# MirZ21.net
KiCad netlist of a schematic drawn in EAGLE
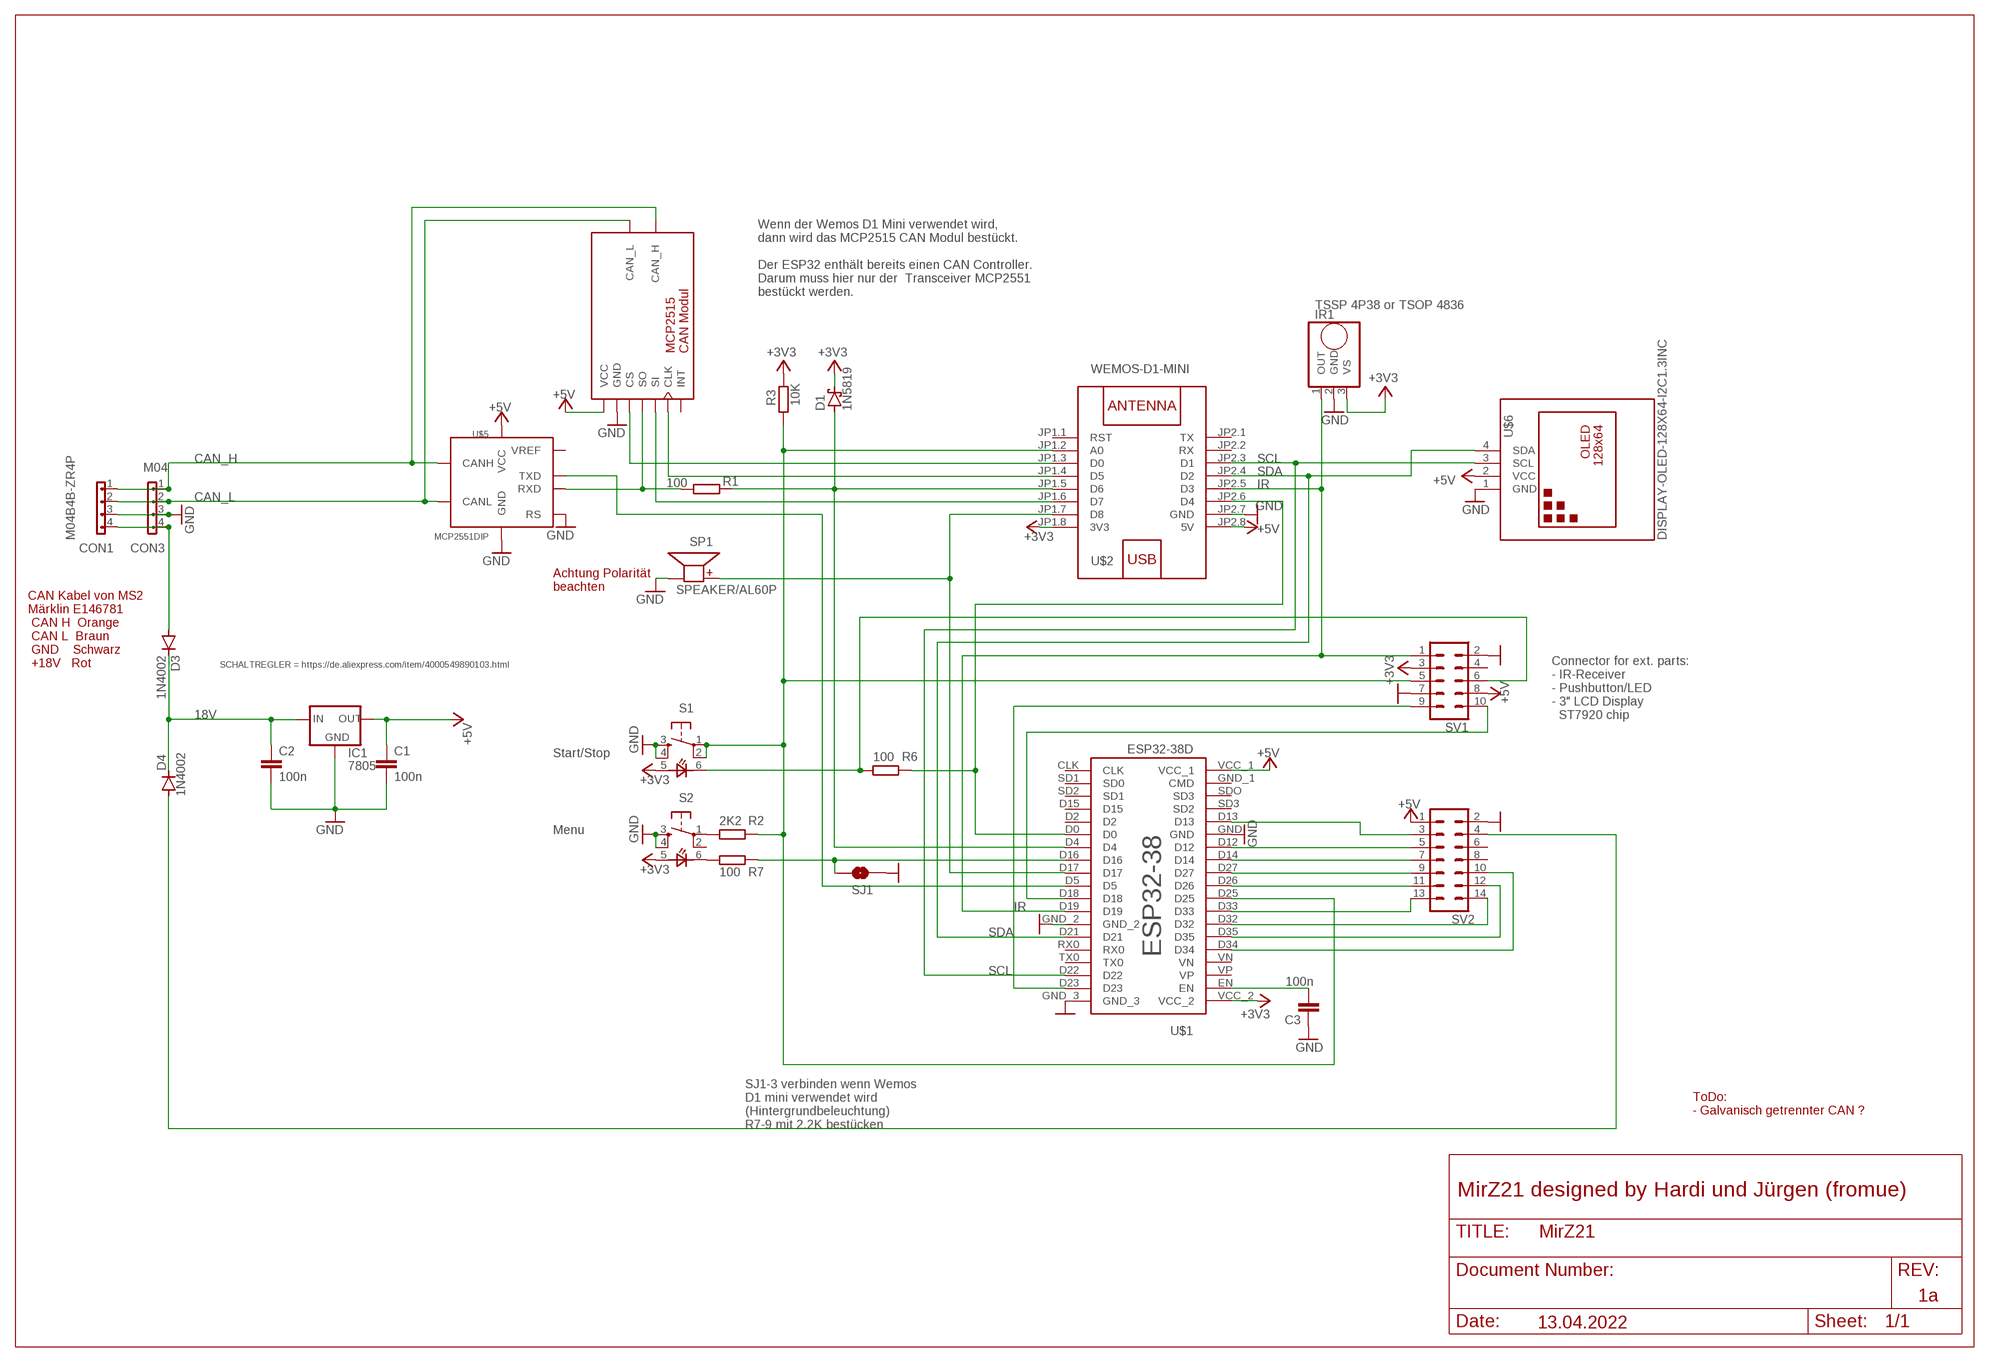
[diagram p0: schematic, sheet 1]

(export (version "E")
  (design (tool "Eeschema 10.0.6"))
  (components
    (comp (ref "C1")
      (value "100n")
      (footprint "eagle-import:C025-025X050")
      (libsource (lib "eagle-import") (part "C-EU025-025X050"))
    )
    (comp (ref "C2")
      (value "100n")
      (footprint "eagle-import:C025-025X050")
      (libsource (lib "eagle-import") (part "C-EU025-025X050"))
    )
    (comp (ref "C3")
      (value "100n")
      (footprint "eagle-import:C025-025X050")
      (libsource (lib "eagle-import") (part "C-EU025-025X050"))
    )
    (comp (ref "CAN1")
      (value "MCP2515_CAN_CUTCUT")
      (footprint "eagle-import:MCP2515_CAN_CUT")
      (libsource (lib "eagle-import") (part "MCP2515_CAN_CUTCUT"))
    )
    (comp (ref "CON1")
      (value "M04B4B-ZR4P")
      (footprint "eagle-import:B4B-ZR4P")
      (libsource (lib "eagle-import") (part "M04B4B-ZR4P"))
    )
    (comp (ref "CON3")
      (value "M04")
      (footprint "eagle-import:1X04")
      (libsource (lib "eagle-import") (part "M04"))
    )
    (comp (ref "D1")
      (value "1N5819")
      (footprint "eagle-import:DO41-7.6")
      (libsource (lib "eagle-import") (part "1N581"))
    )
    (comp (ref "D3")
      (value "1N4002")
      (footprint "eagle-import:DO41-10")
      (libsource (lib "eagle-import") (part "1N4004"))
    )
    (comp (ref "D4")
      (value "1N4002")
      (footprint "eagle-import:DO41-10")
      (libsource (lib "eagle-import") (part "1N4004"))
    )
    (comp (ref "IC1")
      (value "7805")
      (footprint "eagle-import:HX1314G")
      (fields (field (name "SCHALTREGLER") "https://de.aliexpress.com/item/4000549890103.html"))
      (libsource (lib "eagle-import") (part "78XXSSTEPDOWN"))
    )
    (comp (ref "IR1")
      (value "TSSP 4P38 or TSOP 4836")
      (footprint "eagle-import:TSSP4P38")
      (libsource (lib "eagle-import") (part "TSSP4P38"))
    )
    (comp (ref "R1")
      (value "100")
      (footprint "eagle-import:0204_7")
      (libsource (lib "eagle-import") (part "R0204/7"))
    )
    (comp (ref "R2")
      (value "2K2")
      (footprint "eagle-import:0204_7")
      (libsource (lib "eagle-import") (part "R0204/7"))
    )
    (comp (ref "R3")
      (value "10K")
      (footprint "eagle-import:0204_7")
      (libsource (lib "eagle-import") (part "R0204/7"))
    )
    (comp (ref "R6")
      (value "100")
      (footprint "eagle-import:0204_7")
      (libsource (lib "eagle-import") (part "R0204/7"))
    )
    (comp (ref "R7")
      (value "100")
      (footprint "eagle-import:0204_7")
      (libsource (lib "eagle-import") (part "R0204/7"))
    )
    (comp (ref "S1")
      (value "TASTER_LEDTC-1198-B")
      (footprint "eagle-import:TASTER_LED")
      (libsource (lib "eagle-import") (part "TASTER_LEDTC-1198-B"))
    )
    (comp (ref "S2")
      (value "TASTER_LEDTC-1198-B")
      (footprint "eagle-import:TASTER_LED")
      (libsource (lib "eagle-import") (part "TASTER_LEDTC-1198-B"))
    )
    (comp (ref "SJ1")
      (value "SOLDERJUMPERNO")
      (footprint "eagle-import:SJ_2S-NO")
      (libsource (lib "eagle-import") (part "SOLDERJUMPERNO"))
    )
    (comp (ref "SP1")
      (value "SPEAKER/AL60P")
      (footprint "eagle-import:RMP-14SP")
      (libsource (lib "eagle-import") (part "SPEAKER/AL60P"))
    )
    (comp (ref "SV1")
      (value "ML10")
      (footprint "eagle-import:ML10")
      (libsource (lib "eagle-import") (part "ML10"))
    )
    (comp (ref "SV2")
      (value "ML14")
      (footprint "eagle-import:ML14")
      (libsource (lib "eagle-import") (part "ML14"))
    )
    (comp (ref "U$1")
      (value "ESP32-38D")
      (footprint "eagle-import:ESP32-38D")
      (libsource (lib "eagle-import") (part "ESP32-38D"))
    )
    (comp (ref "U$2")
      (value "WEMOS-D1-MINI")
      (footprint "eagle-import:WEMOS-D1-MINI")
      (libsource (lib "eagle-import") (part "WEMOS-D1-MINI"))
    )
    (comp (ref "U$5")
      (value "MCP2551DIP")
      (footprint "eagle-import:DIP08")
      (libsource (lib "eagle-import") (part "MCP2551DIP"))
    )
    (comp (ref "U$6")
      (value "DISPLAY-OLED-128X64-I2C1.3INC")
      (footprint "eagle-import:DISPLAY-OLED-128X64-I2C-1.3")
      (libsource (lib "eagle-import") (part "DISPLAY-OLED-128X64-I2C1.3INC"))
    )
  )
  (nets
    (net (code "1") (name "+3V3") (class "Default")
      (node (ref "D1") (pin "C") (pinfunction "C_C") (pintype "passive"))
      (node (ref "IR1") (pin "3") (pinfunction "VS_3") (pintype "power_in"))
      (node (ref "R3") (pin "2") (pinfunction "2_2") (pintype "passive"))
      (node (ref "S1") (pin "5") (pinfunction "+_5") (pintype "input"))
      (node (ref "S2") (pin "5") (pinfunction "+_5") (pintype "input"))
      (node (ref "SV1") (pin "3") (pinfunction "3_3") (pintype "passive"))
      (node (ref "U$1") (pin "VCC_2") (pinfunction "VCC_2_VCC_2") (pintype "power_in"))
      (node (ref "U$2") (pin "JP1.8") (pinfunction "3V3_JP1.8") (pintype "power_in"))
    )
    (net (code "2") (name "+5V") (class "Default")
      (node (ref "C1") (pin "1") (pinfunction "1_1") (pintype "passive"))
      (node (ref "CAN1") (pin "1") (pinfunction "VCC_1") (pintype "power_in"))
      (node (ref "IC1") (pin "OUT") (pinfunction "OUT_OUT") (pintype "passive"))
      (node (ref "SV1") (pin "8") (pinfunction "8_8") (pintype "passive"))
      (node (ref "SV2") (pin "1") (pinfunction "1_1") (pintype "passive"))
      (node (ref "U$1") (pin "VCC_1") (pinfunction "VCC_1_VCC_1") (pintype "power_in"))
      (node (ref "U$2") (pin "JP2.8") (pinfunction "5V_JP2.8") (pintype "power_in"))
      (node (ref "U$5") (pin "3") (pinfunction "VCC_3") (pintype "power_in"))
      (node (ref "U$6") (pin "2") (pinfunction "VCC_2") (pintype "power_in"))
    )
    (net (code "3") (name "/18V") (class "Default")
      (node (ref "C2") (pin "1") (pinfunction "1_1") (pintype "passive"))
      (node (ref "D3") (pin "C") (pinfunction "C_C") (pintype "passive"))
      (node (ref "D4") (pin "C") (pinfunction "C_C") (pintype "passive"))
      (node (ref "IC1") (pin "IN") (pinfunction "IN_IN") (pintype "input"))
    )
    (net (code "4") (name "/CAN_H") (class "Default")
      (node (ref "CAN1") (pin "9") (pinfunction "CAN_H_9") (pintype "bidirectional"))
      (node (ref "CON1") (pin "1") (pinfunction "1_1") (pintype "passive"))
      (node (ref "CON3") (pin "1") (pinfunction "1_1") (pintype "passive"))
      (node (ref "U$5") (pin "7") (pinfunction "CANH_7") (pintype "bidirectional"))
    )
    (net (code "5") (name "/CAN_L") (class "Default")
      (node (ref "CAN1") (pin "8") (pinfunction "CAN_L_8") (pintype "bidirectional"))
      (node (ref "CON1") (pin "2") (pinfunction "2_2") (pintype "passive"))
      (node (ref "CON3") (pin "2") (pinfunction "2_2") (pintype "passive"))
      (node (ref "U$5") (pin "6") (pinfunction "CANL_6") (pintype "bidirectional"))
    )
    (net (code "6") (name "/IR") (class "Default")
      (node (ref "IR1") (pin "1") (pinfunction "OUT_1") (pintype "output"))
      (node (ref "SV1") (pin "1") (pinfunction "1_1") (pintype "passive"))
      (node (ref "U$1") (pin "D19") (pinfunction "D19_D19") (pintype "bidirectional"))
      (node (ref "U$2") (pin "JP2.5") (pinfunction "D3_JP2.5") (pintype "bidirectional"))
    )
    (net (code "7") (name "/SCL") (class "Default")
      (node (ref "U$1") (pin "D22") (pinfunction "D22_D22") (pintype "bidirectional"))
      (node (ref "U$2") (pin "JP2.3") (pinfunction "D1_JP2.3") (pintype "bidirectional"))
      (node (ref "U$6") (pin "3") (pinfunction "SCL_3") (pintype "bidirectional"))
    )
    (net (code "8") (name "/SDA") (class "Default")
      (node (ref "U$1") (pin "D21") (pinfunction "D21_D21") (pintype "bidirectional"))
      (node (ref "U$2") (pin "JP2.4") (pinfunction "D2_JP2.4") (pintype "bidirectional"))
      (node (ref "U$6") (pin "4") (pinfunction "SDA_4") (pintype "bidirectional"))
    )
    (net (code "9") (name "/VREF") (class "Default")
      (node (ref "U$5") (pin "5") (pinfunction "VREF_5") (pintype "power_in"))
    )
    (net (code "10") (name "GND") (class "Default")
      (node (ref "C1") (pin "2") (pinfunction "2_2") (pintype "passive"))
      (node (ref "C2") (pin "2") (pinfunction "2_2") (pintype "passive"))
      (node (ref "C3") (pin "1") (pinfunction "1_1") (pintype "passive"))
      (node (ref "CAN1") (pin "2") (pinfunction "GND_2") (pintype "power_in"))
      (node (ref "CON1") (pin "3") (pinfunction "3_3") (pintype "passive"))
      (node (ref "CON3") (pin "3") (pinfunction "3_3") (pintype "passive"))
      (node (ref "IC1") (pin "GND") (pinfunction "GND_GND") (pintype "input"))
      (node (ref "IR1") (pin "2") (pinfunction "GND_2") (pintype "power_in"))
      (node (ref "S1") (pin "3") (pinfunction "S_3") (pintype "passive"))
      (node (ref "S1") (pin "4") (pinfunction "S1_4") (pintype "passive"))
      (node (ref "S2") (pin "3") (pinfunction "S_3") (pintype "passive"))
      (node (ref "S2") (pin "4") (pinfunction "S1_4") (pintype "passive"))
      (node (ref "SJ1") (pin "1") (pinfunction "1_1") (pintype "passive"))
      (node (ref "SP1") (pin "2") (pinfunction "-_2") (pintype "passive"))
      (node (ref "SV1") (pin "2") (pinfunction "2_2") (pintype "passive"))
      (node (ref "SV1") (pin "7") (pinfunction "7_7") (pintype "passive"))
      (node (ref "SV2") (pin "2") (pinfunction "2_2") (pintype "passive"))
      (node (ref "U$1") (pin "GND") (pinfunction "GND_GND") (pintype "power_in"))
      (node (ref "U$1") (pin "GND_2") (pinfunction "GND_2_GND_2") (pintype "power_in"))
      (node (ref "U$1") (pin "GND_3") (pinfunction "GND_3_GND_3") (pintype "power_in"))
      (node (ref "U$2") (pin "JP2.7") (pinfunction "GND_JP2.7") (pintype "power_in"))
      (node (ref "U$5") (pin "2") (pinfunction "GND_2") (pintype "power_in"))
      (node (ref "U$5") (pin "8") (pinfunction "RS_8") (pintype "power_in"))
      (node (ref "U$6") (pin "1") (pinfunction "GND_1") (pintype "power_in"))
    )
    (net (code "11") (name "Net-(C3-Pad2)") (class "Default")
      (node (ref "C3") (pin "2") (pinfunction "2_2") (pintype "passive"))
      (node (ref "U$1") (pin "EN") (pinfunction "EN_EN") (pintype "input"))
    )
    (net (code "12") (name "Net-(CAN1-CLK)") (class "Default")
      (node (ref "CAN1") (pin "6") (pinfunction "CLK_6") (pintype "input"))
      (node (ref "U$2") (pin "JP1.4") (pinfunction "D5_JP1.4") (pintype "bidirectional"))
    )
    (net (code "13") (name "Net-(CAN1-CS)") (class "Default")
      (node (ref "CAN1") (pin "3") (pinfunction "CS_3") (pintype "input"))
      (node (ref "U$2") (pin "JP1.3") (pinfunction "D0_JP1.3") (pintype "bidirectional"))
    )
    (net (code "14") (name "Net-(CAN1-SI)") (class "Default")
      (node (ref "CAN1") (pin "5") (pinfunction "SI_5") (pintype "input"))
      (node (ref "U$2") (pin "JP1.6") (pinfunction "D7_JP1.6") (pintype "bidirectional"))
    )
    (net (code "15") (name "Net-(CAN1-SO)") (class "Default")
      (node (ref "CAN1") (pin "4") (pinfunction "SO_4") (pintype "output"))
      (node (ref "R1") (pin "2") (pinfunction "2_2") (pintype "passive"))
      (node (ref "U$5") (pin "4") (pinfunction "RXD_4") (pintype "power_in"))
    )
    (net (code "16") (name "Net-(CON1-Pad4)") (class "Default")
      (node (ref "CON1") (pin "4") (pinfunction "4_4") (pintype "passive"))
      (node (ref "CON3") (pin "4") (pinfunction "4_4") (pintype "passive"))
      (node (ref "D3") (pin "A") (pinfunction "A_A") (pintype "passive"))
    )
    (net (code "17") (name "Net-(D4-PadA)") (class "Default")
      (node (ref "D4") (pin "A") (pinfunction "A_A") (pintype "passive"))
      (node (ref "SV2") (pin "4") (pinfunction "4_4") (pintype "passive"))
    )
    (net (code "18") (name "Net-(R7-Pad1)") (class "Default")
      (node (ref "R7") (pin "1") (pinfunction "1_1") (pintype "passive"))
      (node (ref "SJ1") (pin "2") (pinfunction "2_2") (pintype "passive"))
      (node (ref "U$1") (pin "D16") (pinfunction "D16_D16") (pintype "bidirectional"))
    )
    (net (code "19") (name "Net-(S1--)") (class "Default")
      (node (ref "R6") (pin "2") (pinfunction "2_2") (pintype "passive"))
      (node (ref "S1") (pin "6") (pinfunction "-_6") (pintype "input"))
      (node (ref "SV1") (pin "6") (pinfunction "6_6") (pintype "passive"))
    )
    (net (code "20") (name "Net-(S1-P)") (class "Default")
      (node (ref "R2") (pin "1") (pinfunction "1_1") (pintype "passive"))
      (node (ref "R3") (pin "1") (pinfunction "1_1") (pintype "passive"))
      (node (ref "S1") (pin "1") (pinfunction "P_1") (pintype "passive"))
      (node (ref "S1") (pin "2") (pinfunction "P1_2") (pintype "passive"))
      (node (ref "SV1") (pin "5") (pinfunction "5_5") (pintype "passive"))
      (node (ref "U$1") (pin "D25") (pinfunction "D25_D25") (pintype "bidirectional"))
      (node (ref "U$2") (pin "JP1.2") (pinfunction "A0_JP1.2") (pintype "bidirectional"))
    )
    (net (code "21") (name "Net-(S2--)") (class "Default")
      (node (ref "R7") (pin "2") (pinfunction "2_2") (pintype "passive"))
      (node (ref "S2") (pin "6") (pinfunction "-_6") (pintype "input"))
    )
    (net (code "22") (name "Net-(S2-P)") (class "Default")
      (node (ref "R2") (pin "2") (pinfunction "2_2") (pintype "passive"))
      (node (ref "S2") (pin "1") (pinfunction "P_1") (pintype "passive"))
    )
    (net (code "23") (name "Net-(SP1-+)") (class "Default")
      (node (ref "SP1") (pin "1") (pinfunction "+_1") (pintype "passive"))
      (node (ref "U$1") (pin "D17") (pinfunction "D17_D17") (pintype "bidirectional"))
      (node (ref "U$2") (pin "JP1.7") (pinfunction "D8_JP1.7") (pintype "bidirectional"))
    )
    (net (code "24") (name "Net-(SV1-Pad9)") (class "Default")
      (node (ref "SV1") (pin "9") (pinfunction "9_9") (pintype "passive"))
      (node (ref "U$1") (pin "D23") (pinfunction "D23_D23") (pintype "bidirectional"))
    )
    (net (code "25") (name "Net-(SV1-Pad10)") (class "Default")
      (node (ref "SV1") (pin "10") (pinfunction "10_10") (pintype "passive"))
      (node (ref "U$1") (pin "D18") (pinfunction "D18_D18") (pintype "bidirectional"))
    )
    (net (code "26") (name "Net-(SV2-Pad3)") (class "Default")
      (node (ref "SV2") (pin "3") (pinfunction "3_3") (pintype "passive"))
      (node (ref "U$1") (pin "D13") (pinfunction "D13_D13") (pintype "bidirectional"))
    )
    (net (code "27") (name "Net-(SV2-Pad5)") (class "Default")
      (node (ref "SV2") (pin "5") (pinfunction "5_5") (pintype "passive"))
      (node (ref "U$1") (pin "D12") (pinfunction "D12_D12") (pintype "bidirectional"))
    )
    (net (code "28") (name "Net-(SV2-Pad7)") (class "Default")
      (node (ref "SV2") (pin "7") (pinfunction "7_7") (pintype "passive"))
      (node (ref "U$1") (pin "D14") (pinfunction "D14_D14") (pintype "bidirectional"))
    )
    (net (code "29") (name "Net-(SV2-Pad9)") (class "Default")
      (node (ref "SV2") (pin "9") (pinfunction "9_9") (pintype "passive"))
      (node (ref "U$1") (pin "D27") (pinfunction "D27_D27") (pintype "bidirectional"))
    )
    (net (code "30") (name "Net-(SV2-Pad10)") (class "Default")
      (node (ref "SV2") (pin "10") (pinfunction "10_10") (pintype "passive"))
      (node (ref "U$1") (pin "D34") (pinfunction "D34_D34") (pintype "bidirectional"))
    )
    (net (code "31") (name "Net-(SV2-Pad11)") (class "Default")
      (node (ref "SV2") (pin "11") (pinfunction "11_11") (pintype "passive"))
      (node (ref "U$1") (pin "D26") (pinfunction "D26_D26") (pintype "bidirectional"))
    )
    (net (code "32") (name "Net-(SV2-Pad12)") (class "Default")
      (node (ref "SV2") (pin "12") (pinfunction "12_12") (pintype "passive"))
      (node (ref "U$1") (pin "D35") (pinfunction "D35_D35") (pintype "bidirectional"))
    )
    (net (code "33") (name "Net-(SV2-Pad13)") (class "Default")
      (node (ref "SV2") (pin "13") (pinfunction "13_13") (pintype "passive"))
      (node (ref "U$1") (pin "D33") (pinfunction "D33_D33") (pintype "bidirectional"))
    )
    (net (code "34") (name "Net-(SV2-Pad14)") (class "Default")
      (node (ref "SV2") (pin "14") (pinfunction "14_14") (pintype "passive"))
      (node (ref "U$1") (pin "D32") (pinfunction "D32_D32") (pintype "bidirectional"))
    )
    (net (code "35") (name "Net-(U$2-D4)") (class "Default")
      (node (ref "R6") (pin "1") (pinfunction "1_1") (pintype "passive"))
      (node (ref "U$1") (pin "D0") (pinfunction "D0_D0") (pintype "input"))
      (node (ref "U$2") (pin "JP2.6") (pinfunction "D4_JP2.6") (pintype "bidirectional"))
    )
    (net (code "36") (name "Net-(U$2-D6)") (class "Default")
      (node (ref "D1") (pin "A") (pinfunction "A_A") (pintype "passive"))
      (node (ref "R1") (pin "1") (pinfunction "1_1") (pintype "passive"))
      (node (ref "U$1") (pin "D4") (pinfunction "D4_D4") (pintype "bidirectional"))
      (node (ref "U$2") (pin "JP1.5") (pinfunction "D6_JP1.5") (pintype "bidirectional"))
    )
    (net (code "37") (name "Net-(U$5-TXD)") (class "Default")
      (node (ref "U$1") (pin "D5") (pinfunction "D5_D5") (pintype "bidirectional"))
      (node (ref "U$5") (pin "1") (pinfunction "TXD_1") (pintype "power_in"))
    )
    (net (code "38") (name "unconnected-(CAN1-INT-Pad7)") (class "Default")
      (node (ref "CAN1") (pin "7") (pinfunction "INT_7") (pintype "open_collector"))
    )
    (net (code "39") (name "unconnected-(S2-P1-Pad2)") (class "Default")
      (node (ref "S2") (pin "2") (pinfunction "P1_2") (pintype "passive"))
    )
    (net (code "40") (name "unconnected-(SV1-Pad4)") (class "Default")
      (node (ref "SV1") (pin "4") (pinfunction "4_4") (pintype "passive"))
    )
    (net (code "41") (name "unconnected-(SV2-Pad6)") (class "Default")
      (node (ref "SV2") (pin "6") (pinfunction "6_6") (pintype "passive"))
    )
    (net (code "42") (name "unconnected-(SV2-Pad8)") (class "Default")
      (node (ref "SV2") (pin "8") (pinfunction "8_8") (pintype "passive"))
    )
    (net (code "43") (name "unconnected-(U$1-CMD-PadGND_1)") (class "Default")
      (node (ref "U$1") (pin "GND_1") (pinfunction "CMD_GND_1") (pintype "no_connect"))
    )
    (net (code "44") (name "unconnected-(U$1-PadCLK)") (class "Default")
      (node (ref "U$1") (pin "CLK") (pinfunction "CLK_CLK") (pintype "no_connect"))
    )
    (net (code "45") (name "unconnected-(U$1-PadD2)") (class "Default")
      (node (ref "U$1") (pin "D2") (pinfunction "D2_D2") (pintype "bidirectional"))
    )
    (net (code "46") (name "unconnected-(U$1-PadD15)") (class "Default")
      (node (ref "U$1") (pin "D15") (pinfunction "D15_D15") (pintype "bidirectional"))
    )
    (net (code "47") (name "unconnected-(U$1-PadRX0)") (class "Default")
      (node (ref "U$1") (pin "RX0") (pinfunction "RX0_RX0") (pintype "bidirectional"))
    )
    (net (code "48") (name "unconnected-(U$1-PadTX0)") (class "Default")
      (node (ref "U$1") (pin "TX0") (pinfunction "TX0_TX0") (pintype "bidirectional"))
    )
    (net (code "49") (name "unconnected-(U$1-PadVN)") (class "Default")
      (node (ref "U$1") (pin "VN") (pinfunction "VN_VN") (pintype "bidirectional"))
    )
    (net (code "50") (name "unconnected-(U$1-PadVP)") (class "Default")
      (node (ref "U$1") (pin "VP") (pinfunction "VP_VP") (pintype "bidirectional"))
    )
    (net (code "51") (name "unconnected-(U$1-SD0-PadSD1)") (class "Default")
      (node (ref "U$1") (pin "SD1") (pinfunction "SD0_SD1") (pintype "no_connect"))
    )
    (net (code "52") (name "unconnected-(U$1-SD1-PadSD2)") (class "Default")
      (node (ref "U$1") (pin "SD2") (pinfunction "SD1_SD2") (pintype "no_connect"))
    )
    (net (code "53") (name "unconnected-(U$1-SD2-PadSD3)") (class "Default")
      (node (ref "U$1") (pin "SD3") (pinfunction "SD2_SD3") (pintype "no_connect"))
    )
    (net (code "54") (name "unconnected-(U$1-SD3-PadSDO)") (class "Default")
      (node (ref "U$1") (pin "SDO") (pinfunction "SD3_SDO") (pintype "no_connect"))
    )
    (net (code "55") (name "unconnected-(U$2-RST-PadJP1.1)") (class "Default")
      (node (ref "U$2") (pin "JP1.1") (pinfunction "RST_JP1.1") (pintype "bidirectional"))
    )
    (net (code "56") (name "unconnected-(U$2-RX-PadJP2.2)") (class "Default")
      (node (ref "U$2") (pin "JP2.2") (pinfunction "RX_JP2.2") (pintype "bidirectional"))
    )
    (net (code "57") (name "unconnected-(U$2-TX-PadJP2.1)") (class "Default")
      (node (ref "U$2") (pin "JP2.1") (pinfunction "TX_JP2.1") (pintype "bidirectional"))
    )
  )
)
